# TEMPSENS.net
KiCad netlist of a schematic drawn in Altium Designer
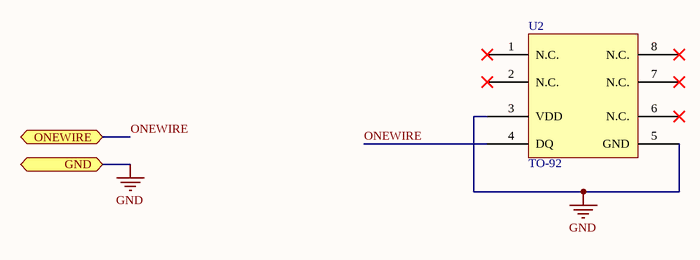
[diagram p0: TEMPSENS.SchDoc]

(export (version "E")
  (design (tool "Eeschema 10.0.6"))
  (components
    (comp (ref "U2") (value "TO-92") (footprint "DS18S20") (libsource (lib "Telemetry") (part "DS18S20")))
  )
  (nets
    (net (code "1") (name "/ONEWIRE") (class "Default")
      (node (ref "U2") (pin "4") (pinfunction "DQ_4") (pintype "passive"))
    )
    (net (code "2") (name "GND") (class "Default")
      (node (ref "U2") (pin "3") (pinfunction "VDD_3") (pintype "passive"))
      (node (ref "U2") (pin "5") (pinfunction "GND_5") (pintype "passive"))
    )
    (net (code "3") (name "unconnected-(U2-N.C.-Pad1)") (class "Default")
      (node (ref "U2") (pin "1") (pinfunction "N.C._1") (pintype "passive+no_connect"))
    )
    (net (code "4") (name "unconnected-(U2-N.C.-Pad2)") (class "Default")
      (node (ref "U2") (pin "2") (pinfunction "N.C._2") (pintype "passive+no_connect"))
    )
    (net (code "5") (name "unconnected-(U2-N.C.-Pad6)") (class "Default")
      (node (ref "U2") (pin "6") (pinfunction "N.C._6") (pintype "passive+no_connect"))
    )
    (net (code "6") (name "unconnected-(U2-N.C.-Pad7)") (class "Default")
      (node (ref "U2") (pin "7") (pinfunction "N.C._7") (pintype "passive+no_connect"))
    )
    (net (code "7") (name "unconnected-(U2-N.C.-Pad8)") (class "Default")
      (node (ref "U2") (pin "8") (pinfunction "N.C._8") (pintype "passive+no_connect"))
    )
  )
)
